# PAGE118.net
KiCad netlist of a schematic drawn in Altium Designer
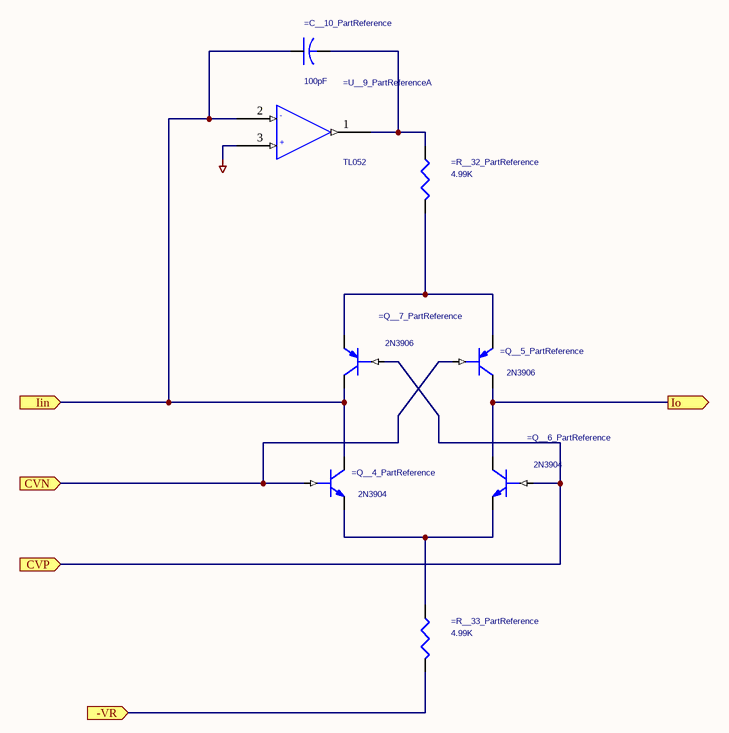
[diagram p0: PAGE118.SchDoc]

(export (version "E")
  (design (tool "Eeschema 10.0.6"))
  (components
    (comp (ref "=C__10_PartReference") (value "100pF") (libsource (lib "*") (part "CAP_Dup1")))
    (comp (ref "=Q__4_PartReference") (value "2N3904") (footprint "TO92") (libsource (lib "*") (part "NPN")))
    (comp (ref "=Q__5_PartReference") (value "2N3906") (footprint "TO92") (libsource (lib "*") (part "PNP")))
    (comp (ref "=Q__6_PartReference") (value "2N3904") (footprint "TO92") (libsource (lib "*") (part "NPN")))
    (comp (ref "=Q__7_PartReference") (value "2N3906") (footprint "TO92") (libsource (lib "*") (part "PNP")))
    (comp (ref "=R__32_PartReference") (value "4.99K") (libsource (lib "*") (part "R_Dup1")))
    (comp (ref "=R__33_PartReference") (value "4.99K") (libsource (lib "*") (part "R_Dup1")))
    (comp (ref "=U__9_PartReference")
      (value "TL052")
      (footprint "DIP8")
      (libsource (lib "*") (part "GEN DUAL OPAMP-H"))
    )
  )
  (nets
    (net (code "1") (name "/-VR") (class "Default")
      (node (ref "=R__33_PartReference") (pin "2") (pinfunction "2_2") (pintype "passive"))
    )
    (net (code "2") (name "/CVN") (class "Default")
      (node (ref "=Q__4_PartReference") (pin "BASE") (pinfunction "BASE_BASE") (pintype "input"))
      (node (ref "=Q__5_PartReference") (pin "BASE") (pinfunction "BASE_BASE") (pintype "input"))
    )
    (net (code "3") (name "/CVP") (class "Default")
      (node (ref "=Q__6_PartReference") (pin "BASE") (pinfunction "BASE_BASE") (pintype "input"))
      (node (ref "=Q__7_PartReference") (pin "BASE") (pinfunction "BASE_BASE") (pintype "input"))
    )
    (net (code "4") (name "/Iin") (class "Default")
      (node (ref "=C__10_PartReference") (pin "1") (pinfunction "1_1") (pintype "passive"))
      (node (ref "=Q__4_PartReference") (pin "COLLECTOR") (pinfunction "COLLECTOR_COLLECTOR") (pintype "passive"))
      (node (ref "=Q__7_PartReference") (pin "COLLECTOR") (pinfunction "COLLECTOR_COLLECTOR") (pintype "passive"))
      (node (ref "=U__9_PartReference") (pin "2") (pinfunction "-_2") (pintype "input"))
    )
    (net (code "5") (name "/Io") (class "Default")
      (node (ref "=Q__5_PartReference") (pin "COLLECTOR") (pinfunction "COLLECTOR_COLLECTOR") (pintype "passive"))
      (node (ref "=Q__6_PartReference") (pin "COLLECTOR") (pinfunction "COLLECTOR_COLLECTOR") (pintype "passive"))
    )
    (net (code "6") (name "AGND") (class "Default")
      (node (ref "=U__9_PartReference") (pin "3") (pinfunction "+_3") (pintype "input"))
    )
    (net (code "7") (name "Net-(=Q__4_PartReference-PadEMITTER)") (class "Default")
      (node (ref "=Q__4_PartReference") (pin "EMITTER") (pinfunction "EMITTER_EMITTER") (pintype "passive"))
      (node (ref "=Q__6_PartReference") (pin "EMITTER") (pinfunction "EMITTER_EMITTER") (pintype "passive"))
      (node (ref "=R__33_PartReference") (pin "1") (pinfunction "1_1") (pintype "passive"))
    )
    (net (code "8") (name "Net-(=Q__5_PartReference-PadEMITTER)") (class "Default")
      (node (ref "=Q__5_PartReference") (pin "EMITTER") (pinfunction "EMITTER_EMITTER") (pintype "passive"))
      (node (ref "=Q__7_PartReference") (pin "EMITTER") (pinfunction "EMITTER_EMITTER") (pintype "passive"))
      (node (ref "=R__32_PartReference") (pin "2") (pinfunction "2_2") (pintype "passive"))
    )
    (net (code "9") (name "Net-(=U__9_PartReferenceA-OUT)") (class "Default")
      (node (ref "=C__10_PartReference") (pin "2") (pinfunction "2_2") (pintype "passive"))
      (node (ref "=R__32_PartReference") (pin "1") (pinfunction "1_1") (pintype "passive"))
      (node (ref "=U__9_PartReference") (pin "1") (pinfunction "OUT_1") (pintype "output"))
    )
  )
)
